# IR_MB.net
KiCad netlist of a schematic drawn in EAGLE
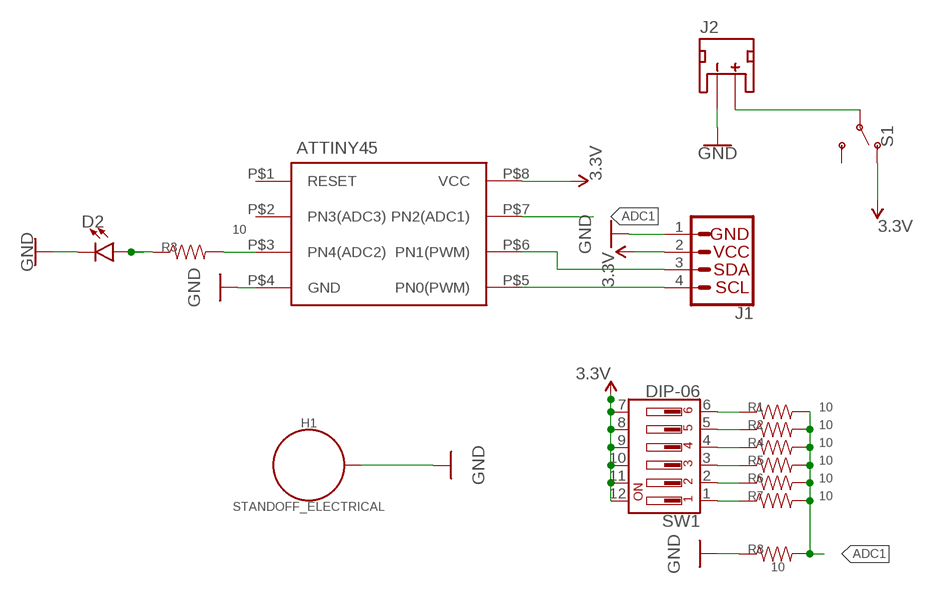
[diagram p0: schematic, sheet 1]

(export (version "E")
  (design (tool "Eeschema 10.0.6"))
  (components
    (comp (ref "D2")
      (value "LED-FKIT-1206")
      (footprint "eagle-import:FKIT-LED-1206")
      (libsource (lib "eagle-import") (part "LED-FKIT-1206"))
    )
    (comp (ref "H1")
      (value "STANDOFF_ELECTRICAL")
      (footprint "eagle-import:STANDOFF-ELECTRICAL")
      (libsource (lib "eagle-import") (part "STANDOFF_ELECTRICAL"))
    )
    (comp (ref "J1")
      (value "QWIIC_CONNECTORJS-1MM")
      (footprint "eagle-import:1X04_1MM_RA")
      (libsource (lib "eagle-import") (part "QWIIC_CONNECTORJS-1MM"))
    )
    (comp (ref "J2")
      (value "JST_2MM_MALE")
      (footprint "eagle-import:JST-2-SMD")
      (libsource (lib "eagle-import") (part "JST_2MM_MALE"))
    )
    (comp (ref "R1")
      (value "10")
      (footprint "eagle-import:1206")
      (libsource (lib "eagle-import") (part "10OHM-1206-1/4W-1%"))
    )
    (comp (ref "R2")
      (value "10")
      (footprint "eagle-import:1206")
      (libsource (lib "eagle-import") (part "10OHM-1206-1/4W-1%"))
    )
    (comp (ref "R3")
      (value "10")
      (footprint "eagle-import:1206")
      (libsource (lib "eagle-import") (part "10OHM-1206-1/4W-1%"))
    )
    (comp (ref "R4")
      (value "10")
      (footprint "eagle-import:1206")
      (libsource (lib "eagle-import") (part "10OHM-1206-1/4W-1%"))
    )
    (comp (ref "R5")
      (value "10")
      (footprint "eagle-import:1206")
      (libsource (lib "eagle-import") (part "10OHM-1206-1/4W-1%"))
    )
    (comp (ref "R6")
      (value "10")
      (footprint "eagle-import:1206")
      (libsource (lib "eagle-import") (part "10OHM-1206-1/4W-1%"))
    )
    (comp (ref "R7")
      (value "10")
      (footprint "eagle-import:1206")
      (libsource (lib "eagle-import") (part "10OHM-1206-1/4W-1%"))
    )
    (comp (ref "R8")
      (value "10")
      (footprint "eagle-import:1206")
      (libsource (lib "eagle-import") (part "10OHM-1206-1/4W-1%"))
    )
    (comp (ref "S1")
      (value "SWITCH-SPDT-PTH-11.6X4.0MM-KIT")
      (footprint "eagle-import:SWITCH_SPDT_PTH_11.6X4.0MM_KIT")
      (libsource (lib "eagle-import") (part "SWITCH-SPDT-PTH-11.6X4.0MM-KIT"))
    )
    (comp (ref "SW1")
      (value "DIP-06")
      (footprint "eagle-import:DIPSWITCH-06-SMD")
      (libsource (lib "eagle-import") (part "DIP-06"))
    )
    (comp (ref "U$1")
      (value "ATTINY45")
      (footprint "eagle-import:8PDIP")
      (libsource (lib "eagle-import") (part "ATTINY45"))
    )
  )
  (nets
    (net (code "1") (name "3.3V") (class "Default")
      (node (ref "J1") (pin "2") (pinfunction "2_2") (pintype "power_in"))
      (node (ref "S1") (pin "1") (pinfunction "O_1") (pintype "passive"))
      (node (ref "SW1") (pin "10") (pinfunction "10_10") (pintype "bidirectional"))
      (node (ref "SW1") (pin "11") (pinfunction "11_11") (pintype "bidirectional"))
      (node (ref "SW1") (pin "12") (pinfunction "12_12") (pintype "bidirectional"))
      (node (ref "SW1") (pin "7") (pinfunction "7_7") (pintype "bidirectional"))
      (node (ref "SW1") (pin "8") (pinfunction "8_8") (pintype "bidirectional"))
      (node (ref "SW1") (pin "9") (pinfunction "9_9") (pintype "bidirectional"))
      (node (ref "U$1") (pin "P$8") (pinfunction "VCC_P$8") (pintype "bidirectional"))
    )
    (net (code "2") (name "ADC1") (class "Default")
      (node (ref "R1") (pin "2") (pinfunction "2_2") (pintype "passive"))
      (node (ref "R2") (pin "2") (pinfunction "2_2") (pintype "passive"))
      (node (ref "R4") (pin "2") (pinfunction "2_2") (pintype "passive"))
      (node (ref "R5") (pin "2") (pinfunction "2_2") (pintype "passive"))
      (node (ref "R6") (pin "2") (pinfunction "2_2") (pintype "passive"))
      (node (ref "R7") (pin "2") (pinfunction "2_2") (pintype "passive"))
      (node (ref "R8") (pin "2") (pinfunction "2_2") (pintype "passive"))
      (node (ref "U$1") (pin "P$7") (pinfunction "PN2(ADC1)_P$7") (pintype "bidirectional"))
    )
    (net (code "3") (name "GND") (class "Default")
      (node (ref "D2") (pin "C") (pinfunction "C_C") (pintype "passive"))
      (node (ref "H1") (pin "P1") (pinfunction "P$1_P1") (pintype "bidirectional"))
      (node (ref "J1") (pin "1") (pinfunction "1_1") (pintype "power_in"))
      (node (ref "J2") (pin "1") (pinfunction "-_1") (pintype "bidirectional"))
      (node (ref "R8") (pin "1") (pinfunction "1_1") (pintype "passive"))
      (node (ref "U$1") (pin "P$4") (pinfunction "GND_P$4") (pintype "bidirectional"))
    )
    (net (code "4") (name "Net-(D2-PadA)") (class "Default")
      (node (ref "D2") (pin "A") (pinfunction "A_A") (pintype "passive"))
      (node (ref "R3") (pin "1") (pinfunction "1_1") (pintype "passive"))
    )
    (net (code "5") (name "Net-(J2-+)") (class "Default")
      (node (ref "J2") (pin "2") (pinfunction "+_2") (pintype "bidirectional"))
      (node (ref "S1") (pin "2") (pinfunction "P_2") (pintype "passive"))
    )
    (net (code "6") (name "Net-(R1-Pad1)") (class "Default")
      (node (ref "R1") (pin "1") (pinfunction "1_1") (pintype "passive"))
      (node (ref "SW1") (pin "6") (pinfunction "6_6") (pintype "bidirectional"))
    )
    (net (code "7") (name "Net-(R2-Pad1)") (class "Default")
      (node (ref "R2") (pin "1") (pinfunction "1_1") (pintype "passive"))
      (node (ref "SW1") (pin "5") (pinfunction "5_5") (pintype "bidirectional"))
    )
    (net (code "8") (name "Net-(R4-Pad1)") (class "Default")
      (node (ref "R4") (pin "1") (pinfunction "1_1") (pintype "passive"))
      (node (ref "SW1") (pin "4") (pinfunction "4_4") (pintype "bidirectional"))
    )
    (net (code "9") (name "Net-(R5-Pad1)") (class "Default")
      (node (ref "R5") (pin "1") (pinfunction "1_1") (pintype "passive"))
      (node (ref "SW1") (pin "3") (pinfunction "3_3") (pintype "bidirectional"))
    )
    (net (code "10") (name "Net-(R6-Pad1)") (class "Default")
      (node (ref "R6") (pin "1") (pinfunction "1_1") (pintype "passive"))
      (node (ref "SW1") (pin "2") (pinfunction "2_2") (pintype "bidirectional"))
    )
    (net (code "11") (name "Net-(R7-Pad1)") (class "Default")
      (node (ref "R7") (pin "1") (pinfunction "1_1") (pintype "passive"))
      (node (ref "SW1") (pin "1") (pinfunction "1_1") (pintype "bidirectional"))
    )
    (net (code "12") (name "Net-(U$1-PN0(PWM))") (class "Default")
      (node (ref "J1") (pin "4") (pinfunction "4_4") (pintype "passive"))
      (node (ref "U$1") (pin "P$5") (pinfunction "PN0(PWM)_P$5") (pintype "bidirectional"))
    )
    (net (code "13") (name "Net-(U$1-PN1(PWM))") (class "Default")
      (node (ref "J1") (pin "3") (pinfunction "3_3") (pintype "passive"))
      (node (ref "U$1") (pin "P$6") (pinfunction "PN1(PWM)_P$6") (pintype "bidirectional"))
    )
    (net (code "14") (name "Net-(U$1-PN4(ADC2))") (class "Default")
      (node (ref "R3") (pin "2") (pinfunction "2_2") (pintype "passive"))
      (node (ref "U$1") (pin "P$3") (pinfunction "PN4(ADC2)_P$3") (pintype "bidirectional"))
    )
    (net (code "15") (name "unconnected-(J2-PAD1-PadNC1)") (class "Default")
      (node (ref "J2") (pin "NC1") (pinfunction "PAD1_NC1") (pintype "bidirectional"))
    )
    (net (code "16") (name "unconnected-(J2-PAD2-PadNC2)") (class "Default")
      (node (ref "J2") (pin "NC2") (pinfunction "PAD2_NC2") (pintype "bidirectional"))
    )
    (net (code "17") (name "unconnected-(S1-S-Pad3)") (class "Default")
      (node (ref "S1") (pin "3") (pinfunction "S_3") (pintype "passive"))
    )
    (net (code "18") (name "unconnected-(U$1-PN3(ADC3)-PadP$2)") (class "Default")
      (node (ref "U$1") (pin "P$2") (pinfunction "PN3(ADC3)_P$2") (pintype "bidirectional"))
    )
    (net (code "19") (name "unconnected-(U$1-RESET-PadP$1)") (class "Default")
      (node (ref "U$1") (pin "P$1") (pinfunction "RESET_P$1") (pintype "bidirectional"))
    )
  )
)
